# shiftReg1.net
KiCad netlist of a schematic drawn in Altium Designer
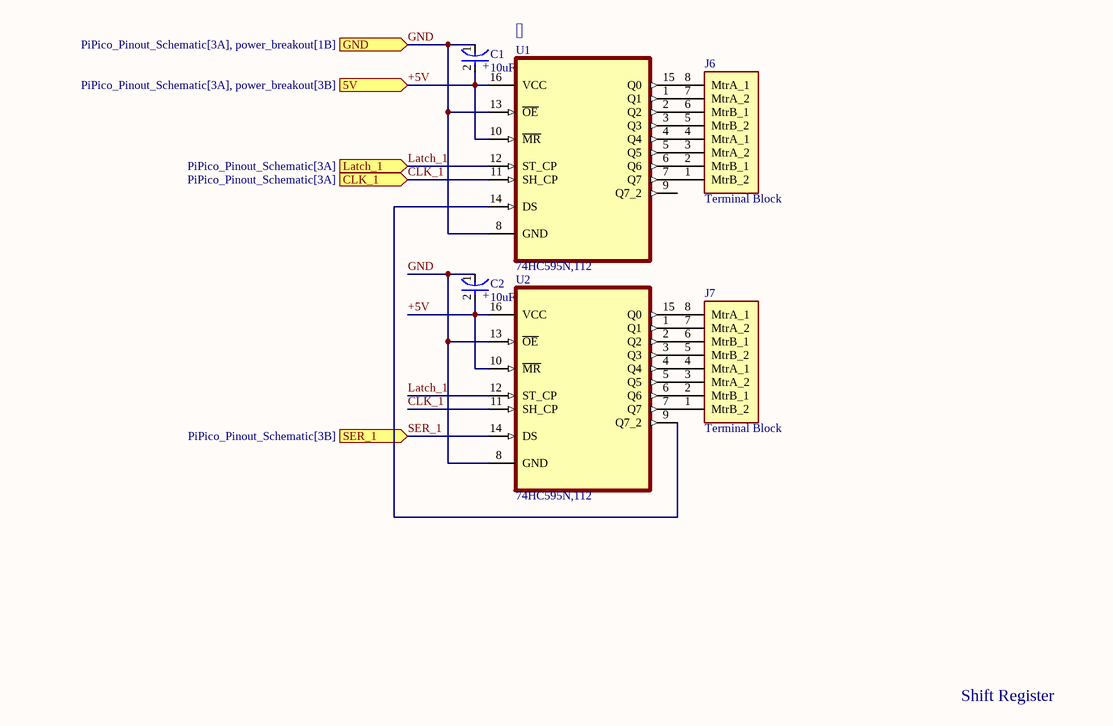
[diagram p0: shiftReg1.SchDoc]

(export (version "E")
  (design (tool "Eeschema 10.0.6"))
  (components
    (comp (ref "C1")
      (value "10uF")
      (footprint "FP-TAP106K016SCS-MFG")
      (description "CAP TANT 10UF 10% 16V RADIAL")
      (fields (field (name "TOLERANCE") "10%") (field (name "VOLTAGE") "16V"))
      (libsource (lib "Altium Content Vault") (part "cf48714ba7e38822c1575c7ec0b6d1f"))
    )
    (comp (ref "C2")
      (value "10uF")
      (footprint "FP-TAP106K016SCS-MFG")
      (description "CAP TANT 10UF 10% 16V RADIAL")
      (fields (field (name "TOLERANCE") "10%") (field (name "VOLTAGE") "16V"))
      (libsource (lib "Altium Content Vault") (part "cf48714ba7e38822c1575c7ec0b6d1f"))
    )
    (comp (ref "J6")
      (value "Terminal Block")
      (footprint "TE_282834-8")
      (description "Buchanan; Conn; Term Blk; PCB; 8; 2.54mm; Front; 30-16 AWG; Green; 10 A; 150 V")
      (fields (field (name "MF") "TE Connectivity") (field (name "DIGI-KEY_PART_NUMBER") "A98338-ND"))
      (libsource (lib "8pin_ScrewTerminal_2.54mm") (part "282834-8"))
    )
    (comp (ref "J7")
      (value "Terminal Block")
      (footprint "TE_282834-8")
      (description "Buchanan; Conn; Term Blk; PCB; 8; 2.54mm; Front; 30-16 AWG; Green; 10 A; 150 V")
      (fields (field (name "MF") "TE Connectivity") (field (name "DIGI-KEY_PART_NUMBER") "A98338-ND"))
      (libsource (lib "8pin_ScrewTerminal_2.54mm") (part "282834-8"))
    )
    (comp (ref "U1")
      (value "74HC595N,112")
      (footprint "DIP254P762X420-16")
      (description "Shift Shift Register 1 Element 8 Bit 16-DIP")
      (fields (field (name "MF") "NXP USA"))
      (libsource (lib "74HC595N_112") (part "74HC595N,112"))
    )
    (comp (ref "U2")
      (value "74HC595N,112")
      (footprint "DIP254P762X420-16")
      (description "Shift Shift Register 1 Element 8 Bit 16-DIP")
      (fields (field (name "MF") "NXP USA"))
      (libsource (lib "74HC595N_112") (part "74HC595N,112"))
    )
  )
  (nets
    (net (code "1") (name "/+5V") (class "Default")
      (node (ref "C1") (pin "2") (pinfunction "A_2") (pintype "passive"))
      (node (ref "C2") (pin "2") (pinfunction "A_2") (pintype "passive"))
      (node (ref "U1") (pin "10") (pinfunction "~{MR}_10") (pintype "input"))
      (node (ref "U1") (pin "16") (pinfunction "VCC_16") (pintype "power_in"))
      (node (ref "U2") (pin "10") (pinfunction "~{MR}_10") (pintype "input"))
      (node (ref "U2") (pin "16") (pinfunction "VCC_16") (pintype "power_in"))
    )
    (net (code "2") (name "/CLK_1") (class "Default")
      (node (ref "U1") (pin "11") (pinfunction "SH_CP_11") (pintype "input"))
      (node (ref "U2") (pin "11") (pinfunction "SH_CP_11") (pintype "input"))
    )
    (net (code "3") (name "/GND") (class "Default")
      (node (ref "C1") (pin "1") (pinfunction "C_1") (pintype "passive"))
      (node (ref "C2") (pin "1") (pinfunction "C_1") (pintype "passive"))
      (node (ref "U1") (pin "13") (pinfunction "~{OE}_13") (pintype "input"))
      (node (ref "U1") (pin "8") (pinfunction "GND_8") (pintype "passive"))
      (node (ref "U2") (pin "13") (pinfunction "~{OE}_13") (pintype "input"))
      (node (ref "U2") (pin "8") (pinfunction "GND_8") (pintype "passive"))
    )
    (net (code "4") (name "/Latch_1") (class "Default")
      (node (ref "U1") (pin "12") (pinfunction "ST_CP_12") (pintype "input"))
      (node (ref "U2") (pin "12") (pinfunction "ST_CP_12") (pintype "input"))
    )
    (net (code "5") (name "/SER_1") (class "Default")
      (node (ref "U2") (pin "14") (pinfunction "DS_14") (pintype "input"))
    )
    (net (code "6") (name "Net-(U1-DS)") (class "Default")
      (node (ref "U1") (pin "14") (pinfunction "DS_14") (pintype "input"))
      (node (ref "U2") (pin "9") (pinfunction "Q7_2_9") (pintype "output"))
    )
    (net (code "7") (name "Net-(U1-Q0)") (class "Default")
      (node (ref "J6") (pin "8") (pinfunction "MtrA_1_8") (pintype "passive"))
      (node (ref "U1") (pin "15") (pinfunction "Q0_15") (pintype "output"))
    )
    (net (code "8") (name "Net-(U1-Q1)") (class "Default")
      (node (ref "J6") (pin "7") (pinfunction "MtrA_2_7") (pintype "passive"))
      (node (ref "U1") (pin "1") (pinfunction "Q1_1") (pintype "output"))
    )
    (net (code "9") (name "Net-(U1-Q2)") (class "Default")
      (node (ref "J6") (pin "6") (pinfunction "MtrB_1_6") (pintype "passive"))
      (node (ref "U1") (pin "2") (pinfunction "Q2_2") (pintype "output"))
    )
    (net (code "10") (name "Net-(U1-Q3)") (class "Default")
      (node (ref "J6") (pin "5") (pinfunction "MtrB_2_5") (pintype "passive"))
      (node (ref "U1") (pin "3") (pinfunction "Q3_3") (pintype "output"))
    )
    (net (code "11") (name "Net-(U1-Q4)") (class "Default")
      (node (ref "J6") (pin "4") (pinfunction "MtrA_1_4") (pintype "passive"))
      (node (ref "U1") (pin "4") (pinfunction "Q4_4") (pintype "output"))
    )
    (net (code "12") (name "Net-(U1-Q5)") (class "Default")
      (node (ref "J6") (pin "3") (pinfunction "MtrA_2_3") (pintype "passive"))
      (node (ref "U1") (pin "5") (pinfunction "Q5_5") (pintype "output"))
    )
    (net (code "13") (name "Net-(U1-Q6)") (class "Default")
      (node (ref "J6") (pin "2") (pinfunction "MtrB_1_2") (pintype "passive"))
      (node (ref "U1") (pin "6") (pinfunction "Q6_6") (pintype "output"))
    )
    (net (code "14") (name "Net-(U1-Q7)") (class "Default")
      (node (ref "J6") (pin "1") (pinfunction "MtrB_2_1") (pintype "passive"))
      (node (ref "U1") (pin "7") (pinfunction "Q7_7") (pintype "output"))
    )
    (net (code "15") (name "Net-(U2-Q0)") (class "Default")
      (node (ref "J7") (pin "8") (pinfunction "MtrA_1_8") (pintype "passive"))
      (node (ref "U2") (pin "15") (pinfunction "Q0_15") (pintype "output"))
    )
    (net (code "16") (name "Net-(U2-Q1)") (class "Default")
      (node (ref "J7") (pin "7") (pinfunction "MtrA_2_7") (pintype "passive"))
      (node (ref "U2") (pin "1") (pinfunction "Q1_1") (pintype "output"))
    )
    (net (code "17") (name "Net-(U2-Q2)") (class "Default")
      (node (ref "J7") (pin "6") (pinfunction "MtrB_1_6") (pintype "passive"))
      (node (ref "U2") (pin "2") (pinfunction "Q2_2") (pintype "output"))
    )
    (net (code "18") (name "Net-(U2-Q3)") (class "Default")
      (node (ref "J7") (pin "5") (pinfunction "MtrB_2_5") (pintype "passive"))
      (node (ref "U2") (pin "3") (pinfunction "Q3_3") (pintype "output"))
    )
    (net (code "19") (name "Net-(U2-Q4)") (class "Default")
      (node (ref "J7") (pin "4") (pinfunction "MtrA_1_4") (pintype "passive"))
      (node (ref "U2") (pin "4") (pinfunction "Q4_4") (pintype "output"))
    )
    (net (code "20") (name "Net-(U2-Q5)") (class "Default")
      (node (ref "J7") (pin "3") (pinfunction "MtrA_2_3") (pintype "passive"))
      (node (ref "U2") (pin "5") (pinfunction "Q5_5") (pintype "output"))
    )
    (net (code "21") (name "Net-(U2-Q6)") (class "Default")
      (node (ref "J7") (pin "2") (pinfunction "MtrB_1_2") (pintype "passive"))
      (node (ref "U2") (pin "6") (pinfunction "Q6_6") (pintype "output"))
    )
    (net (code "22") (name "Net-(U2-Q7)") (class "Default")
      (node (ref "J7") (pin "1") (pinfunction "MtrB_2_1") (pintype "passive"))
      (node (ref "U2") (pin "7") (pinfunction "Q7_7") (pintype "output"))
    )
    (net (code "23") (name "unconnected-(U1-Q7_2-Pad9)") (class "Default")
      (node (ref "U1") (pin "9") (pinfunction "Q7_2_9") (pintype "output"))
    )
  )
)
